# Efis_Korry.net
KiCad netlist of a schematic drawn in EasyEDA
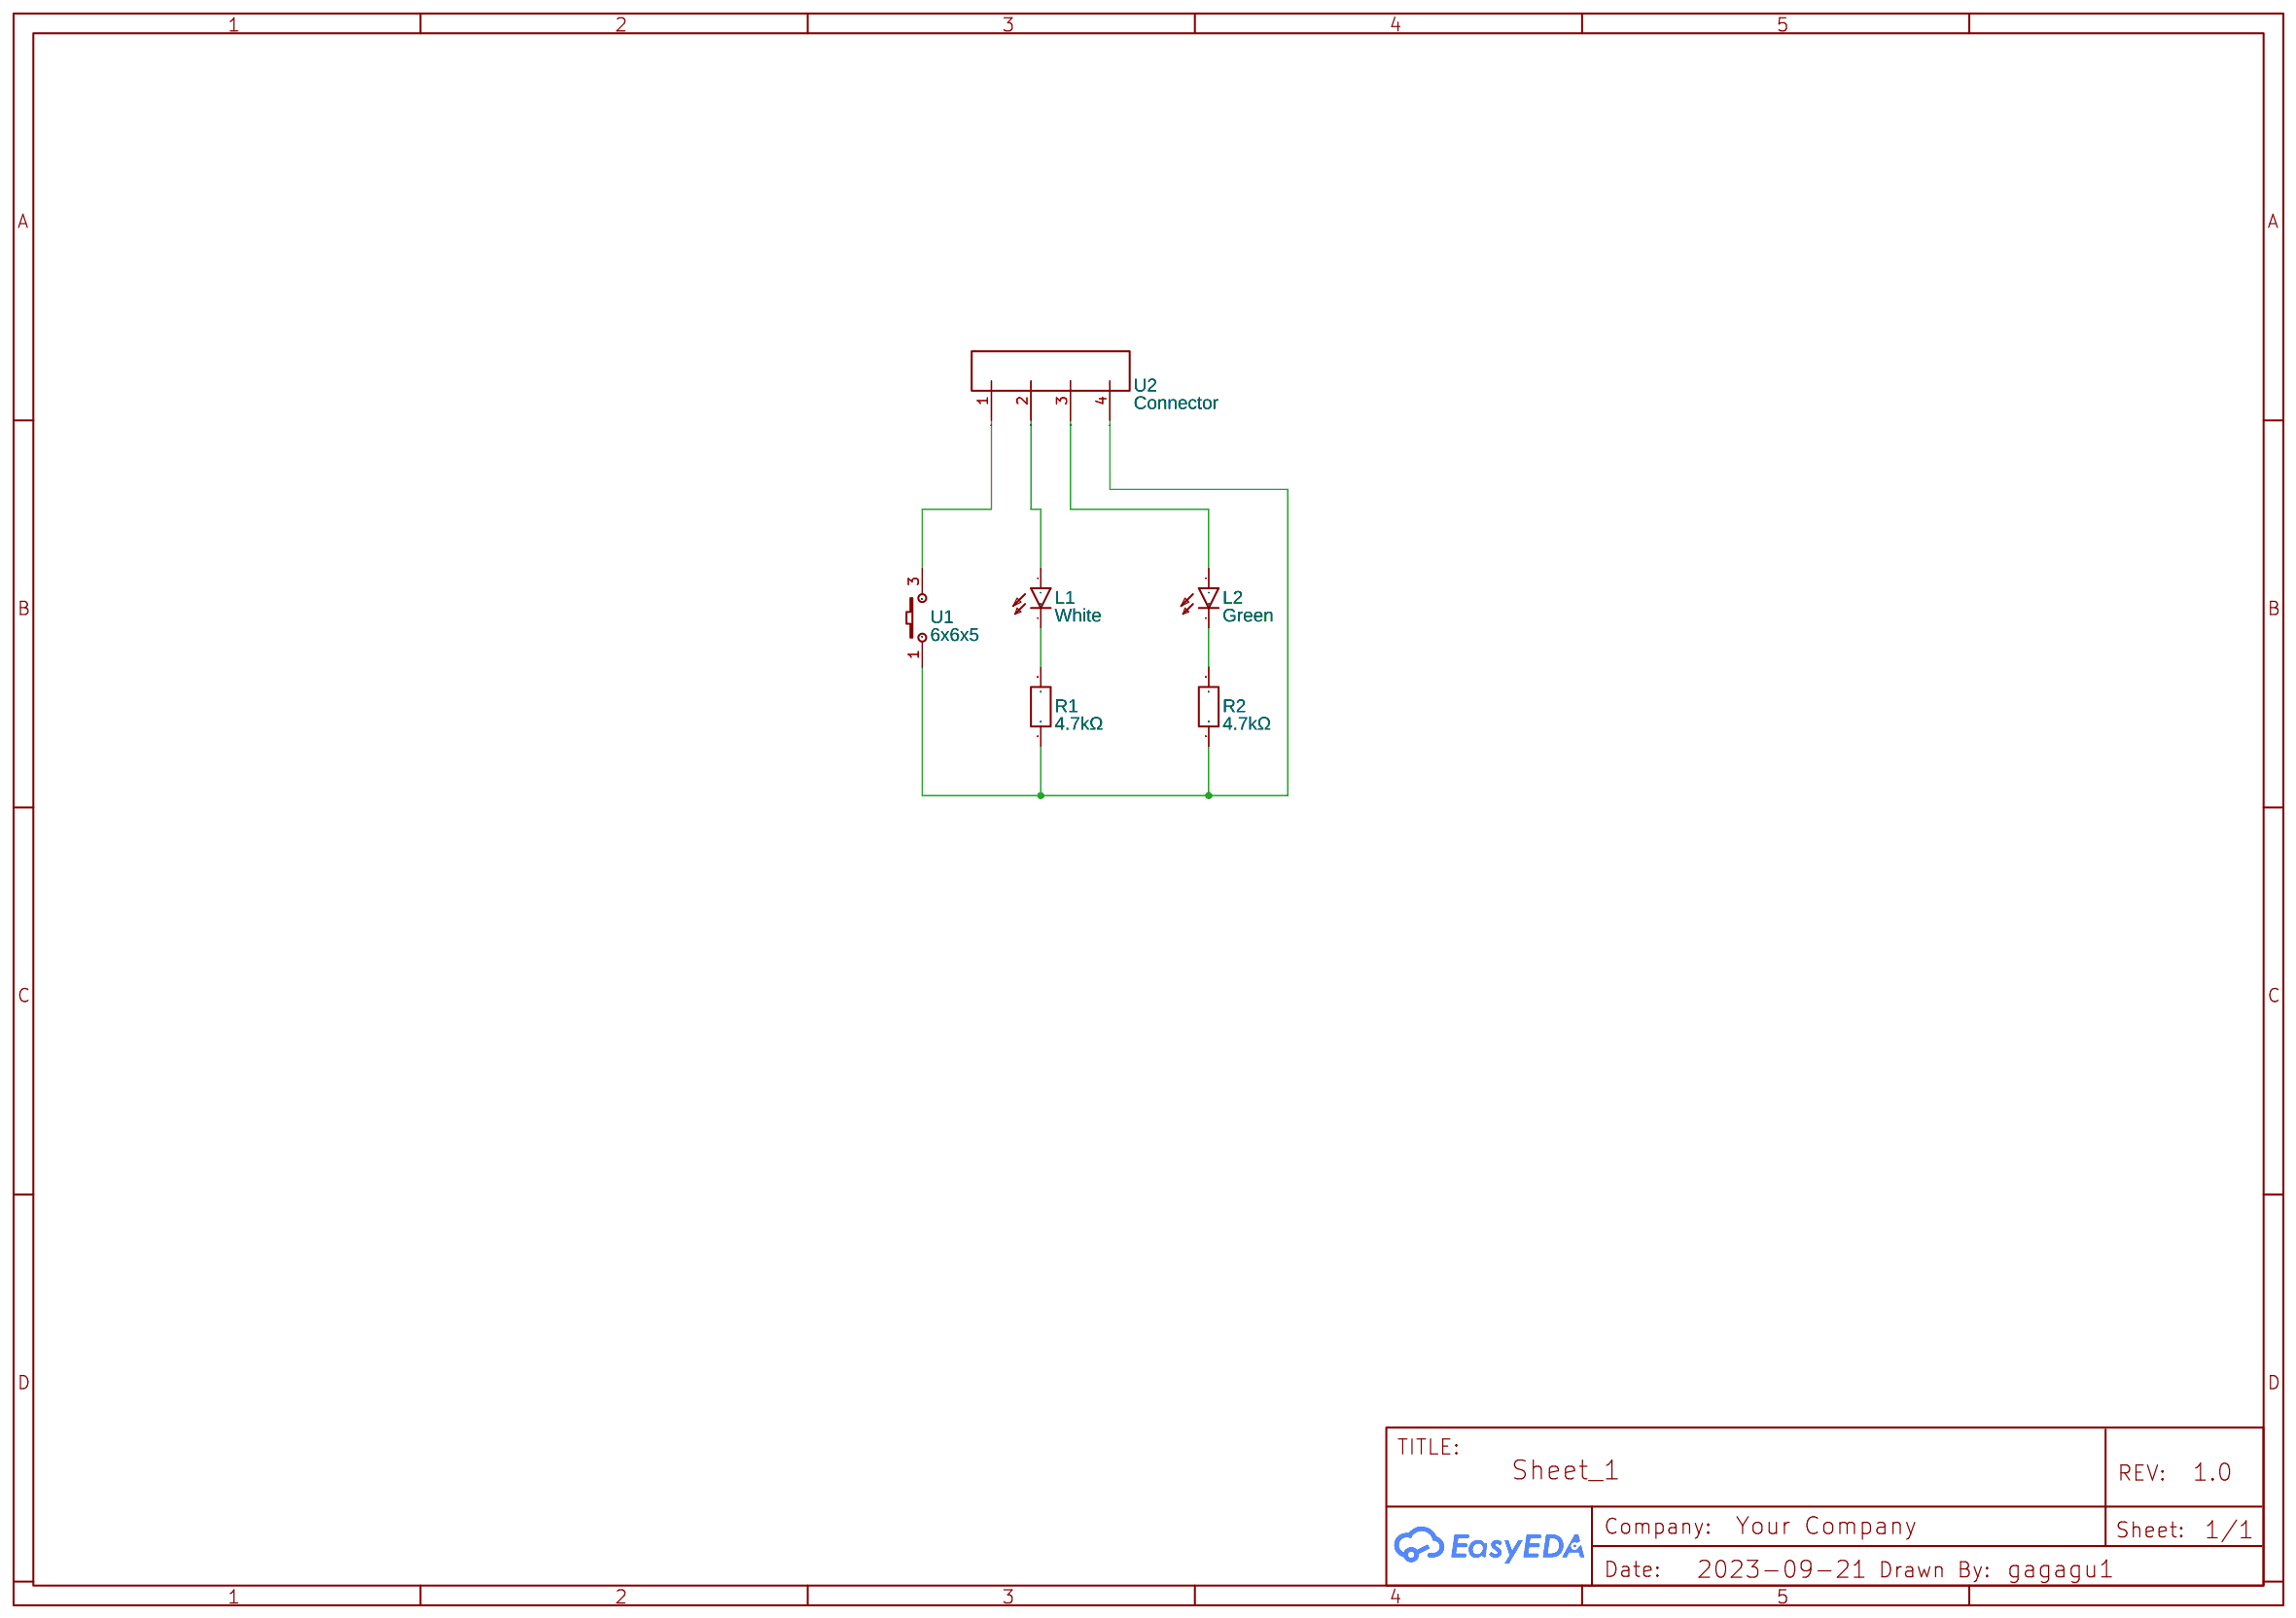
[diagram p0: schematic sheet]

(export (version "E")
  (design (tool "Eeschema 10.0.6"))
  (components
    (comp (ref "L1") (value "White") (libsource (lib "") (part "LED3MM")))
    (comp (ref "L2") (value "Green") (libsource (lib "") (part "LED3MM")))
    (comp (ref "R1")
      (value "4.7kΩ")
      (fields (field (name "Manufacturer Part") "FRC0603F4701TS") (field (name "Manufacturer") "FOJAN(富捷)"))
      (libsource (lib "") (part "FRC0603F4701TS"))
    )
    (comp (ref "R2")
      (value "4.7kΩ")
      (fields (field (name "Manufacturer Part") "FRC0603F4701TS") (field (name "Manufacturer") "FOJAN(富捷)"))
      (libsource (lib "") (part "FRC0603F4701TS"))
    )
    (comp (ref "U1") (value "6x6x5") (libsource (lib "") (part "tlačítko 6*6*5")))
    (comp (ref "U2") (value "Connector") (libsource (lib "") (part "4pinMaleConnector-kafi")))
  )
  (nets
    (net (code "1") (name "Net-(L1-C)") (class "Default")
      (node (ref "L1") (pin "K") (pinfunction "C_K") (pintype "bidirectional"))
      (node (ref "R1") (pin "2") (pinfunction "2_2") (pintype "unspecified"))
    )
    (net (code "2") (name "Net-(L1-PadA)") (class "Default")
      (node (ref "L1") (pin "A") (pinfunction "A_A") (pintype "bidirectional"))
      (node (ref "U2") (pin "2") (pinfunction "2_2") (pintype "unspecified"))
    )
    (net (code "3") (name "Net-(L2-C)") (class "Default")
      (node (ref "L2") (pin "K") (pinfunction "C_K") (pintype "bidirectional"))
      (node (ref "R2") (pin "2") (pinfunction "2_2") (pintype "unspecified"))
    )
    (net (code "4") (name "Net-(L2-PadA)") (class "Default")
      (node (ref "L2") (pin "A") (pinfunction "A_A") (pintype "bidirectional"))
      (node (ref "U2") (pin "3") (pinfunction "3_3") (pintype "unspecified"))
    )
    (net (code "5") (name "Net-(R1-Pad1)") (class "Default")
      (node (ref "R1") (pin "1") (pinfunction "1_1") (pintype "unspecified"))
      (node (ref "R2") (pin "1") (pinfunction "1_1") (pintype "unspecified"))
      (node (ref "U1") (pin "1") (pinfunction "1_1") (pintype "unspecified"))
      (node (ref "U2") (pin "4") (pinfunction "4_4") (pintype "unspecified"))
    )
    (net (code "6") (name "Net-(U1-Pad3)") (class "Default")
      (node (ref "U1") (pin "3") (pinfunction "3_3") (pintype "unspecified"))
      (node (ref "U2") (pin "1") (pinfunction "1_1") (pintype "unspecified"))
    )
  )
)
